# arduino_pins.net
KiCad netlist of a schematic drawn in EAGLE
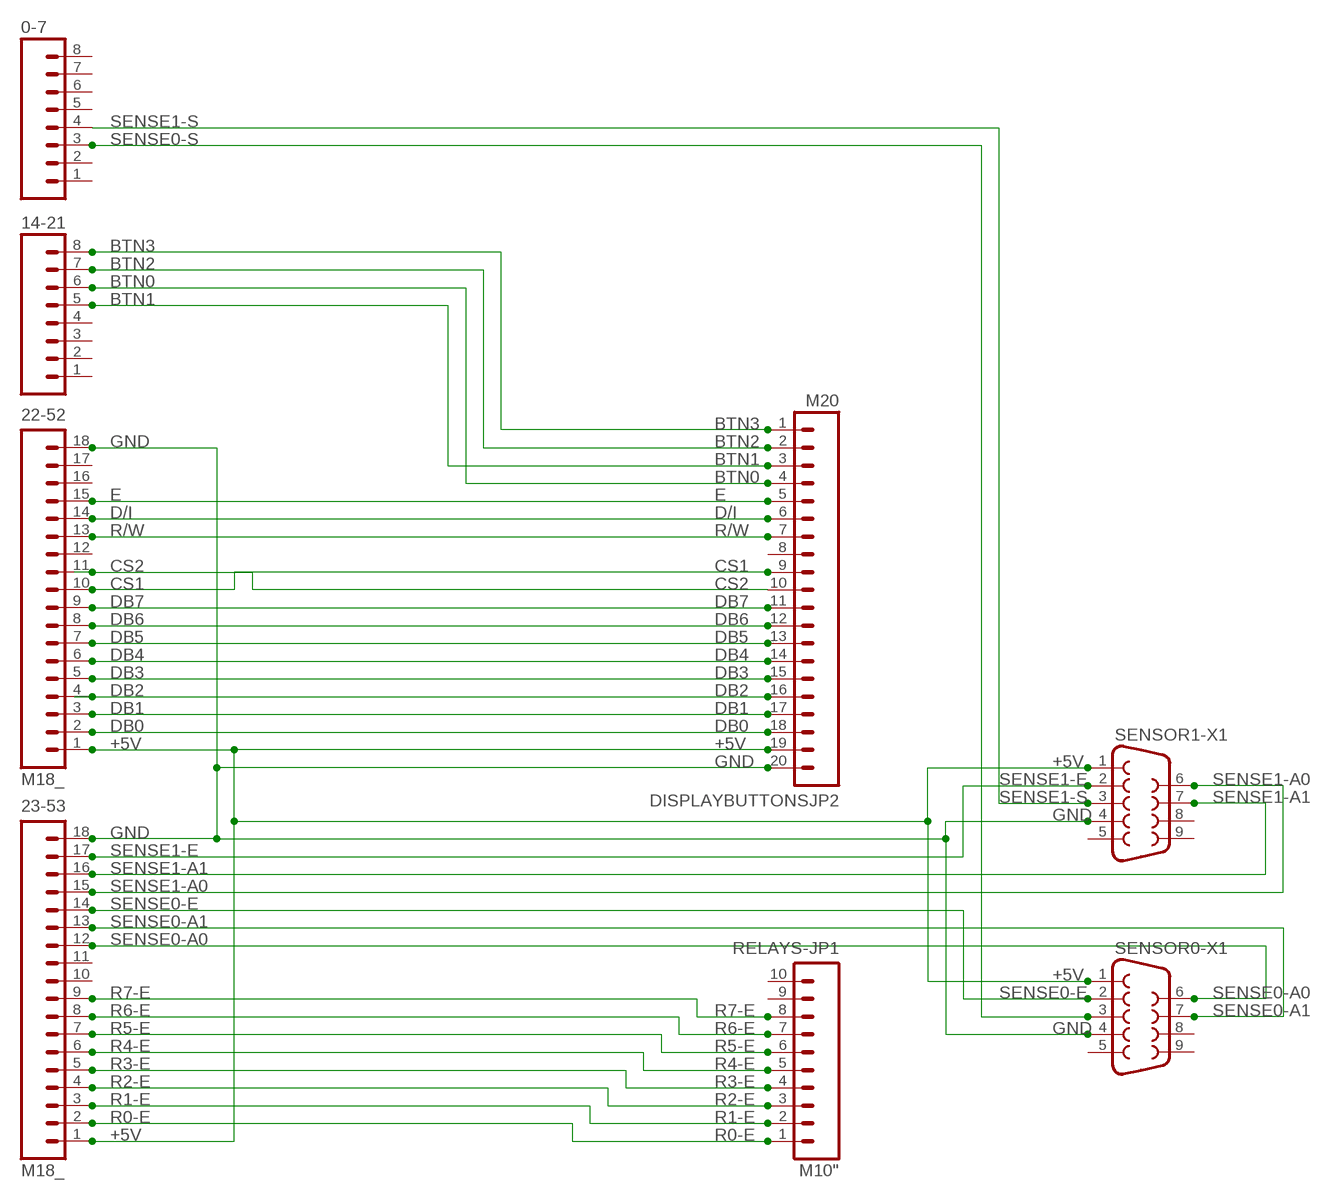
[diagram p0: schematic, sheet 1]

(export (version "E")
  (design (tool "Eeschema 10.0.6"))
  (components
    (comp (ref "0-7")
      (value "M081X08")
      (footprint "eagle-import:1X08")
      (libsource (lib "eagle-import") (part "M081X08"))
    )
    (comp (ref "14-21")
      (value "M081X08")
      (footprint "eagle-import:1X08")
      (libsource (lib "eagle-import") (part "M081X08"))
    )
    (comp (ref "22-52")
      (value "M18_")
      (footprint "eagle-import:1X18")
      (libsource (lib "eagle-import") (part "M18_"))
    )
    (comp (ref "23-53")
      (value "M18_")
      (footprint "eagle-import:1X18")
      (libsource (lib "eagle-import") (part "M18_"))
    )
    (comp (ref "DISPLAYBUTTONSJP2")
      (value "M20")
      (footprint "eagle-import:1X20")
      (libsource (lib "eagle-import") (part "M20"))
    )
    (comp (ref "RELAYS-JP1")
      (value "M10\"")
      (footprint "eagle-import:1X10")
      (libsource (lib "eagle-import") (part "M10{dblquote}"))
    )
    (comp (ref "SENSOR0-X1")
      (value "DB9MALE")
      (footprint "eagle-import:DB9_MALE")
      (libsource (lib "eagle-import") (part "DB9MALE"))
    )
    (comp (ref "SENSOR1-X1")
      (value "DB9MALE")
      (footprint "eagle-import:DB9_MALE")
      (libsource (lib "eagle-import") (part "DB9MALE"))
    )
  )
  (nets
    (net (code "1") (name "/+5V") (class "Default")
      (node (ref "22-52") (pin "1") (pinfunction "1_1") (pintype "passive"))
      (node (ref "23-53") (pin "1") (pinfunction "1_1") (pintype "passive"))
      (node (ref "DISPLAYBUTTONSJP2") (pin "19") (pinfunction "19_19") (pintype "passive"))
      (node (ref "SENSOR0-X1") (pin "1") (pinfunction "1_1") (pintype "passive"))
      (node (ref "SENSOR1-X1") (pin "1") (pinfunction "1_1") (pintype "passive"))
    )
    (net (code "2") (name "/BTN0") (class "Default")
      (node (ref "14-21") (pin "6") (pinfunction "6_6") (pintype "passive"))
      (node (ref "DISPLAYBUTTONSJP2") (pin "4") (pinfunction "4_4") (pintype "passive"))
    )
    (net (code "3") (name "/BTN1") (class "Default")
      (node (ref "14-21") (pin "5") (pinfunction "5_5") (pintype "passive"))
      (node (ref "DISPLAYBUTTONSJP2") (pin "3") (pinfunction "3_3") (pintype "passive"))
    )
    (net (code "4") (name "/BTN2") (class "Default")
      (node (ref "14-21") (pin "7") (pinfunction "7_7") (pintype "passive"))
      (node (ref "DISPLAYBUTTONSJP2") (pin "2") (pinfunction "2_2") (pintype "passive"))
    )
    (net (code "5") (name "/BTN3") (class "Default")
      (node (ref "14-21") (pin "8") (pinfunction "8_8") (pintype "passive"))
      (node (ref "DISPLAYBUTTONSJP2") (pin "1") (pinfunction "1_1") (pintype "passive"))
    )
    (net (code "6") (name "/CS1") (class "Default")
      (node (ref "22-52") (pin "10") (pinfunction "10_10") (pintype "passive"))
      (node (ref "DISPLAYBUTTONSJP2") (pin "9") (pinfunction "9_9") (pintype "passive"))
    )
    (net (code "7") (name "/CS2") (class "Default")
      (node (ref "22-52") (pin "11") (pinfunction "11_11") (pintype "passive"))
      (node (ref "DISPLAYBUTTONSJP2") (pin "10") (pinfunction "10_10") (pintype "passive"))
    )
    (net (code "8") (name "/DB0") (class "Default")
      (node (ref "22-52") (pin "2") (pinfunction "2_2") (pintype "passive"))
      (node (ref "DISPLAYBUTTONSJP2") (pin "18") (pinfunction "18_18") (pintype "passive"))
    )
    (net (code "9") (name "/DB1") (class "Default")
      (node (ref "22-52") (pin "3") (pinfunction "3_3") (pintype "passive"))
      (node (ref "DISPLAYBUTTONSJP2") (pin "17") (pinfunction "17_17") (pintype "passive"))
    )
    (net (code "10") (name "/DB2") (class "Default")
      (node (ref "22-52") (pin "4") (pinfunction "4_4") (pintype "passive"))
      (node (ref "DISPLAYBUTTONSJP2") (pin "16") (pinfunction "16_16") (pintype "passive"))
    )
    (net (code "11") (name "/DB3") (class "Default")
      (node (ref "22-52") (pin "5") (pinfunction "5_5") (pintype "passive"))
      (node (ref "DISPLAYBUTTONSJP2") (pin "15") (pinfunction "15_15") (pintype "passive"))
    )
    (net (code "12") (name "/DB4") (class "Default")
      (node (ref "22-52") (pin "6") (pinfunction "6_6") (pintype "passive"))
      (node (ref "DISPLAYBUTTONSJP2") (pin "14") (pinfunction "14_14") (pintype "passive"))
    )
    (net (code "13") (name "/DB5") (class "Default")
      (node (ref "22-52") (pin "7") (pinfunction "7_7") (pintype "passive"))
      (node (ref "DISPLAYBUTTONSJP2") (pin "13") (pinfunction "13_13") (pintype "passive"))
    )
    (net (code "14") (name "/DB6") (class "Default")
      (node (ref "22-52") (pin "8") (pinfunction "8_8") (pintype "passive"))
      (node (ref "DISPLAYBUTTONSJP2") (pin "12") (pinfunction "12_12") (pintype "passive"))
    )
    (net (code "15") (name "/DB7") (class "Default")
      (node (ref "22-52") (pin "9") (pinfunction "9_9") (pintype "passive"))
      (node (ref "DISPLAYBUTTONSJP2") (pin "11") (pinfunction "11_11") (pintype "passive"))
    )
    (net (code "16") (name "/D{slash}I") (class "Default")
      (node (ref "22-52") (pin "14") (pinfunction "14_14") (pintype "passive"))
      (node (ref "DISPLAYBUTTONSJP2") (pin "6") (pinfunction "6_6") (pintype "passive"))
    )
    (net (code "17") (name "/E") (class "Default")
      (node (ref "22-52") (pin "15") (pinfunction "15_15") (pintype "passive"))
      (node (ref "DISPLAYBUTTONSJP2") (pin "5") (pinfunction "5_5") (pintype "passive"))
    )
    (net (code "18") (name "/GND") (class "Default")
      (node (ref "22-52") (pin "18") (pinfunction "18_18") (pintype "passive"))
      (node (ref "23-53") (pin "18") (pinfunction "18_18") (pintype "passive"))
      (node (ref "DISPLAYBUTTONSJP2") (pin "20") (pinfunction "20_20") (pintype "passive"))
      (node (ref "SENSOR0-X1") (pin "4") (pinfunction "4_4") (pintype "passive"))
      (node (ref "SENSOR1-X1") (pin "4") (pinfunction "4_4") (pintype "passive"))
    )
    (net (code "19") (name "/R0-E") (class "Default")
      (node (ref "23-53") (pin "2") (pinfunction "2_2") (pintype "passive"))
      (node (ref "RELAYS-JP1") (pin "1") (pinfunction "1_1") (pintype "passive"))
    )
    (net (code "20") (name "/R1-E") (class "Default")
      (node (ref "23-53") (pin "3") (pinfunction "3_3") (pintype "passive"))
      (node (ref "RELAYS-JP1") (pin "2") (pinfunction "2_2") (pintype "passive"))
    )
    (net (code "21") (name "/R2-E") (class "Default")
      (node (ref "23-53") (pin "4") (pinfunction "4_4") (pintype "passive"))
      (node (ref "RELAYS-JP1") (pin "3") (pinfunction "3_3") (pintype "passive"))
    )
    (net (code "22") (name "/R3-E") (class "Default")
      (node (ref "23-53") (pin "5") (pinfunction "5_5") (pintype "passive"))
      (node (ref "RELAYS-JP1") (pin "4") (pinfunction "4_4") (pintype "passive"))
    )
    (net (code "23") (name "/R4-E") (class "Default")
      (node (ref "23-53") (pin "6") (pinfunction "6_6") (pintype "passive"))
      (node (ref "RELAYS-JP1") (pin "5") (pinfunction "5_5") (pintype "passive"))
    )
    (net (code "24") (name "/R5-E") (class "Default")
      (node (ref "23-53") (pin "7") (pinfunction "7_7") (pintype "passive"))
      (node (ref "RELAYS-JP1") (pin "6") (pinfunction "6_6") (pintype "passive"))
    )
    (net (code "25") (name "/R6-E") (class "Default")
      (node (ref "23-53") (pin "8") (pinfunction "8_8") (pintype "passive"))
      (node (ref "RELAYS-JP1") (pin "7") (pinfunction "7_7") (pintype "passive"))
    )
    (net (code "26") (name "/R7-E") (class "Default")
      (node (ref "23-53") (pin "9") (pinfunction "9_9") (pintype "passive"))
      (node (ref "RELAYS-JP1") (pin "8") (pinfunction "8_8") (pintype "passive"))
    )
    (net (code "27") (name "/R{slash}W") (class "Default")
      (node (ref "22-52") (pin "13") (pinfunction "13_13") (pintype "passive"))
      (node (ref "DISPLAYBUTTONSJP2") (pin "7") (pinfunction "7_7") (pintype "passive"))
    )
    (net (code "28") (name "/SENSE0-A0") (class "Default")
      (node (ref "23-53") (pin "12") (pinfunction "12_12") (pintype "passive"))
      (node (ref "SENSOR0-X1") (pin "6") (pinfunction "6_6") (pintype "passive"))
    )
    (net (code "29") (name "/SENSE0-A1") (class "Default")
      (node (ref "23-53") (pin "13") (pinfunction "13_13") (pintype "passive"))
      (node (ref "SENSOR0-X1") (pin "7") (pinfunction "7_7") (pintype "passive"))
    )
    (net (code "30") (name "/SENSE0-E") (class "Default")
      (node (ref "23-53") (pin "14") (pinfunction "14_14") (pintype "passive"))
      (node (ref "SENSOR0-X1") (pin "2") (pinfunction "2_2") (pintype "passive"))
    )
    (net (code "31") (name "/SENSE0-S") (class "Default")
      (node (ref "0-7") (pin "3") (pinfunction "3_3") (pintype "passive"))
      (node (ref "SENSOR0-X1") (pin "3") (pinfunction "3_3") (pintype "passive"))
    )
    (net (code "32") (name "/SENSE1-A0") (class "Default")
      (node (ref "23-53") (pin "15") (pinfunction "15_15") (pintype "passive"))
      (node (ref "SENSOR1-X1") (pin "6") (pinfunction "6_6") (pintype "passive"))
    )
    (net (code "33") (name "/SENSE1-A1") (class "Default")
      (node (ref "23-53") (pin "16") (pinfunction "16_16") (pintype "passive"))
      (node (ref "SENSOR1-X1") (pin "7") (pinfunction "7_7") (pintype "passive"))
    )
    (net (code "34") (name "/SENSE1-E") (class "Default")
      (node (ref "23-53") (pin "17") (pinfunction "17_17") (pintype "passive"))
      (node (ref "SENSOR1-X1") (pin "2") (pinfunction "2_2") (pintype "passive"))
    )
    (net (code "35") (name "/SENSE1-S") (class "Default")
      (node (ref "0-7") (pin "4") (pinfunction "4_4") (pintype "passive"))
      (node (ref "SENSOR1-X1") (pin "3") (pinfunction "3_3") (pintype "passive"))
    )
    (net (code "36") (name "unconnected-(0-7-Pad1)") (class "Default")
      (node (ref "0-7") (pin "1") (pinfunction "1_1") (pintype "passive"))
    )
    (net (code "37") (name "unconnected-(0-7-Pad2)") (class "Default")
      (node (ref "0-7") (pin "2") (pinfunction "2_2") (pintype "passive"))
    )
    (net (code "38") (name "unconnected-(0-7-Pad5)") (class "Default")
      (node (ref "0-7") (pin "5") (pinfunction "5_5") (pintype "passive"))
    )
    (net (code "39") (name "unconnected-(0-7-Pad6)") (class "Default")
      (node (ref "0-7") (pin "6") (pinfunction "6_6") (pintype "passive"))
    )
    (net (code "40") (name "unconnected-(0-7-Pad7)") (class "Default")
      (node (ref "0-7") (pin "7") (pinfunction "7_7") (pintype "passive"))
    )
    (net (code "41") (name "unconnected-(0-7-Pad8)") (class "Default")
      (node (ref "0-7") (pin "8") (pinfunction "8_8") (pintype "passive"))
    )
    (net (code "42") (name "unconnected-(14-21-Pad1)") (class "Default")
      (node (ref "14-21") (pin "1") (pinfunction "1_1") (pintype "passive"))
    )
    (net (code "43") (name "unconnected-(14-21-Pad2)") (class "Default")
      (node (ref "14-21") (pin "2") (pinfunction "2_2") (pintype "passive"))
    )
    (net (code "44") (name "unconnected-(14-21-Pad3)") (class "Default")
      (node (ref "14-21") (pin "3") (pinfunction "3_3") (pintype "passive"))
    )
    (net (code "45") (name "unconnected-(14-21-Pad4)") (class "Default")
      (node (ref "14-21") (pin "4") (pinfunction "4_4") (pintype "passive"))
    )
    (net (code "46") (name "unconnected-(22-52-Pad12)") (class "Default")
      (node (ref "22-52") (pin "12") (pinfunction "12_12") (pintype "passive"))
    )
    (net (code "47") (name "unconnected-(22-52-Pad16)") (class "Default")
      (node (ref "22-52") (pin "16") (pinfunction "16_16") (pintype "passive"))
    )
    (net (code "48") (name "unconnected-(22-52-Pad17)") (class "Default")
      (node (ref "22-52") (pin "17") (pinfunction "17_17") (pintype "passive"))
    )
    (net (code "49") (name "unconnected-(23-53-Pad10)") (class "Default")
      (node (ref "23-53") (pin "10") (pinfunction "10_10") (pintype "passive"))
    )
    (net (code "50") (name "unconnected-(23-53-Pad11)") (class "Default")
      (node (ref "23-53") (pin "11") (pinfunction "11_11") (pintype "passive"))
    )
    (net (code "51") (name "unconnected-(DISPLAYBUTTONSJP2-Pad8)") (class "Default")
      (node (ref "DISPLAYBUTTONSJP2") (pin "8") (pinfunction "8_8") (pintype "passive"))
    )
    (net (code "52") (name "unconnected-(RELAYS-JP1-Pad9)") (class "Default")
      (node (ref "RELAYS-JP1") (pin "9") (pinfunction "9_9") (pintype "passive"))
    )
    (net (code "53") (name "unconnected-(RELAYS-JP1-Pad10)") (class "Default")
      (node (ref "RELAYS-JP1") (pin "10") (pinfunction "10_10") (pintype "passive"))
    )
    (net (code "54") (name "unconnected-(SENSOR0-X1-Pad5)") (class "Default")
      (node (ref "SENSOR0-X1") (pin "5") (pinfunction "5_5") (pintype "passive"))
    )
    (net (code "55") (name "unconnected-(SENSOR0-X1-Pad8)") (class "Default")
      (node (ref "SENSOR0-X1") (pin "8") (pinfunction "8_8") (pintype "passive"))
    )
    (net (code "56") (name "unconnected-(SENSOR0-X1-Pad9)") (class "Default")
      (node (ref "SENSOR0-X1") (pin "9") (pinfunction "9_9") (pintype "passive"))
    )
    (net (code "57") (name "unconnected-(SENSOR1-X1-Pad5)") (class "Default")
      (node (ref "SENSOR1-X1") (pin "5") (pinfunction "5_5") (pintype "passive"))
    )
    (net (code "58") (name "unconnected-(SENSOR1-X1-Pad8)") (class "Default")
      (node (ref "SENSOR1-X1") (pin "8") (pinfunction "8_8") (pintype "passive"))
    )
    (net (code "59") (name "unconnected-(SENSOR1-X1-Pad9)") (class "Default")
      (node (ref "SENSOR1-X1") (pin "9") (pinfunction "9_9") (pintype "passive"))
    )
  )
)
